# RoverWing-V4b.net
KiCad netlist of a schematic drawn in EAGLE
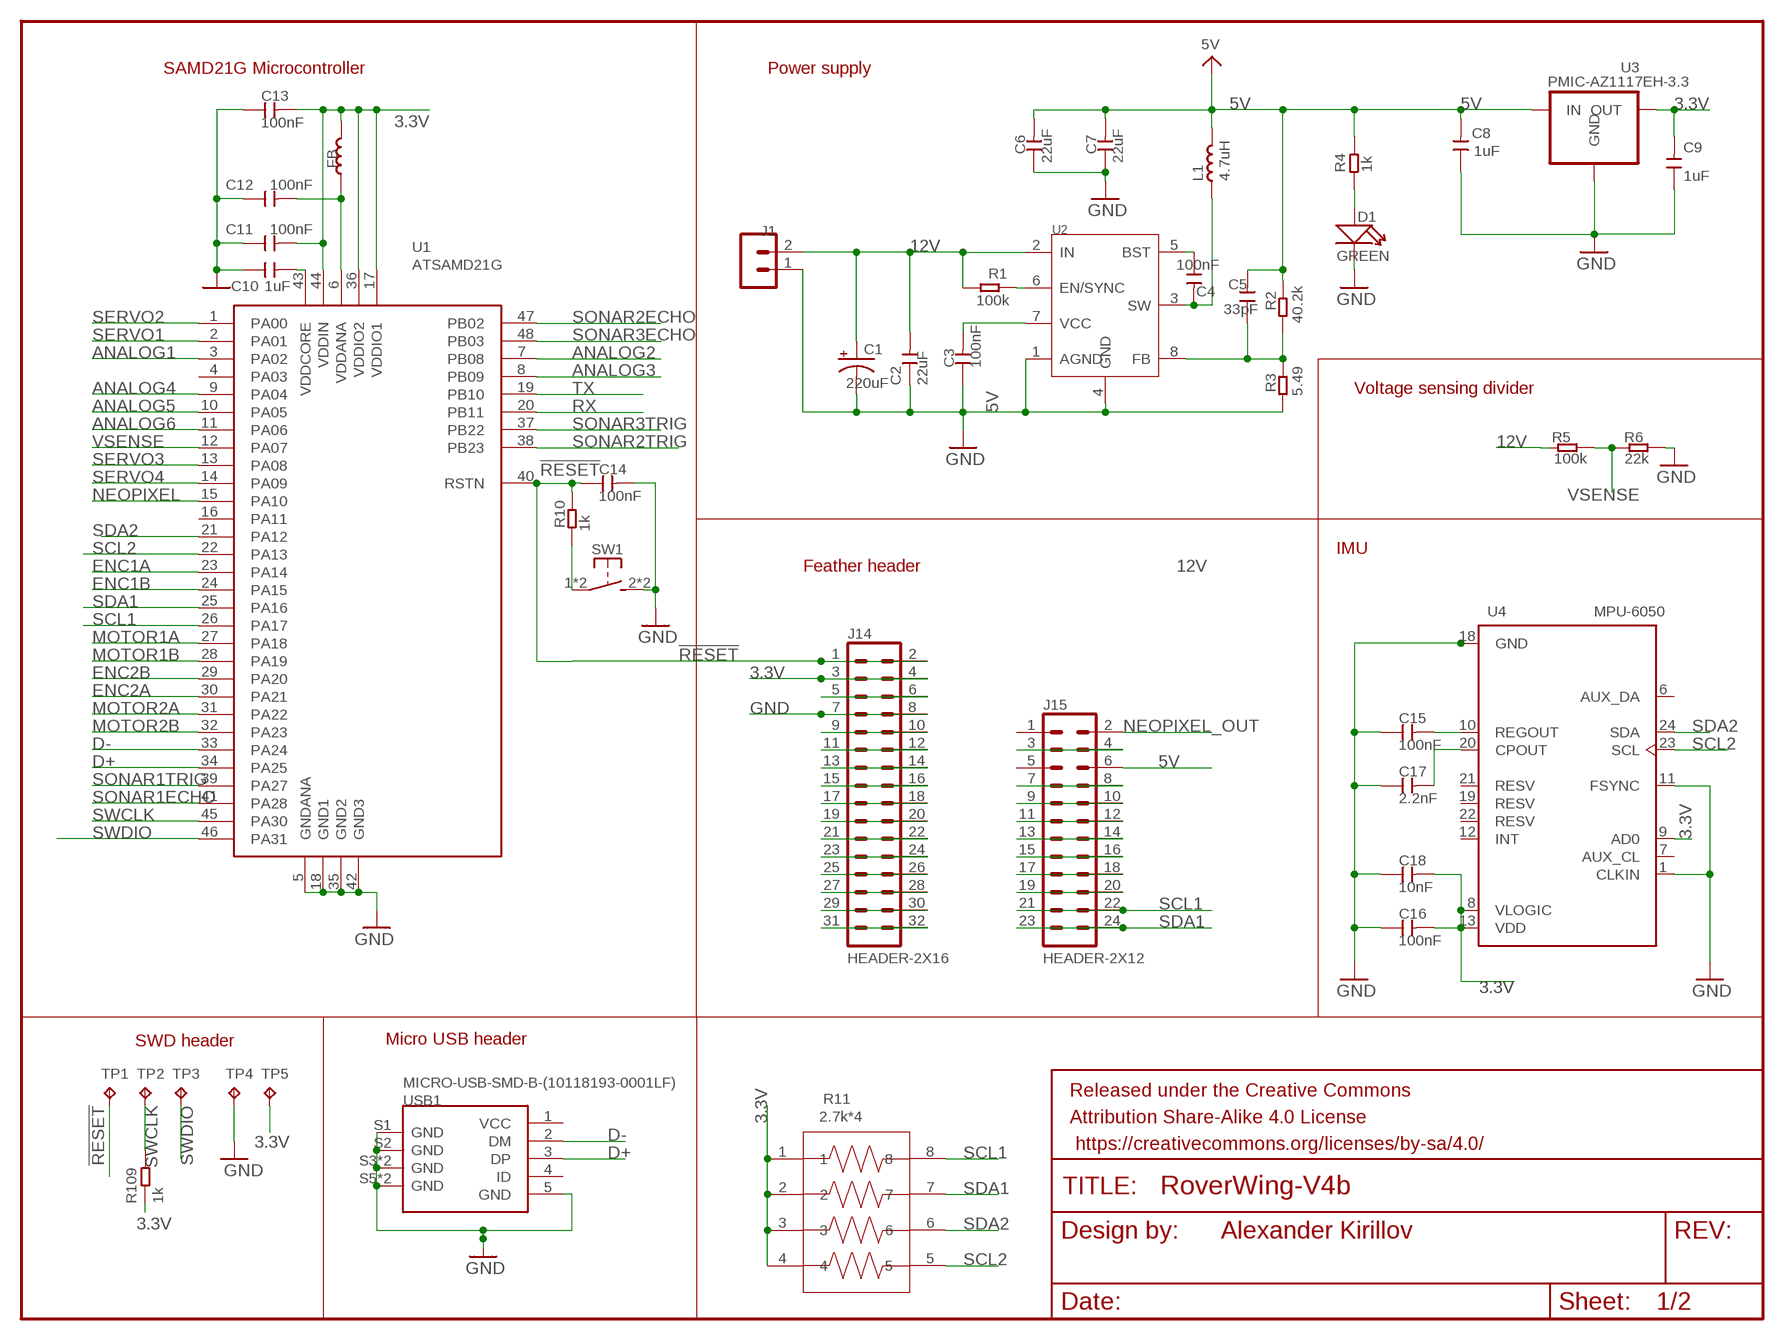
[diagram p0: schematic, sheet 1]
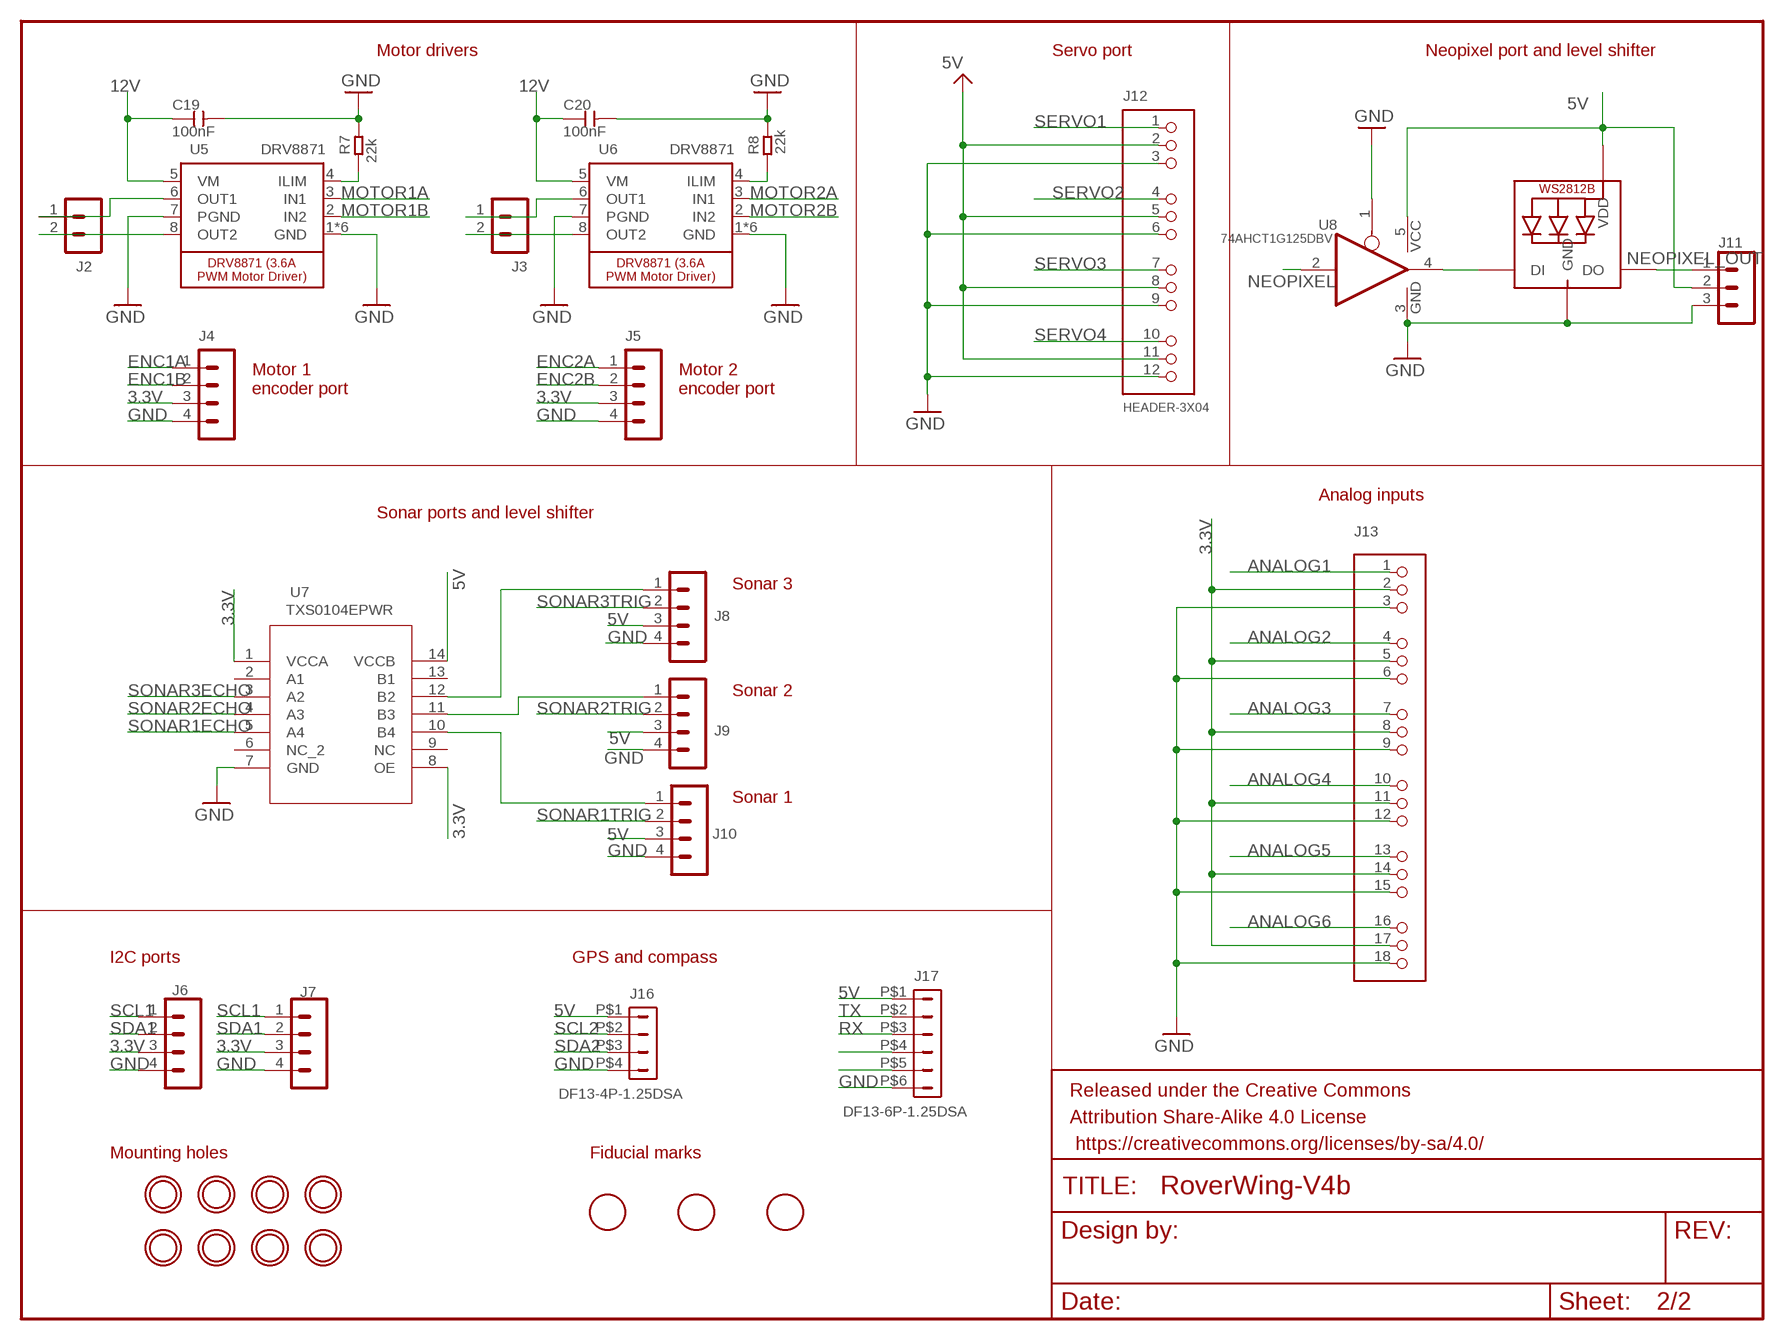
[diagram p1: schematic, sheet 2]

(export (version "E")
  (design (tool "Eeschema 10.0.6"))
  (components
    (comp (ref "C1")
      (value "220uF")
      (footprint "eagle-import:CAP-8X10.5")
      (libsource (lib "eagle-import") (part "CAP-POL-SMD-8X10.5"))
    )
    (comp (ref "C2")
      (value "22uF")
      (footprint "eagle-import:0805")
      (libsource (lib "eagle-import") (part "CAP-CERAMIC-SMD0805"))
    )
    (comp (ref "C3")
      (value "100nF")
      (footprint "eagle-import:0805")
      (libsource (lib "eagle-import") (part "CAP-CERAMIC-SMD0805"))
    )
    (comp (ref "C4")
      (value "100nF")
      (footprint "eagle-import:0805")
      (libsource (lib "eagle-import") (part "CAP-CERAMIC-SMD0805"))
    )
    (comp (ref "C5")
      (value "33pF")
      (footprint "eagle-import:0805")
      (libsource (lib "eagle-import") (part "CAP-CERAMIC-SMD0805"))
    )
    (comp (ref "C6")
      (value "22uF")
      (footprint "eagle-import:0805")
      (libsource (lib "eagle-import") (part "CAP-CERAMIC-SMD0805"))
    )
    (comp (ref "C7")
      (value "22uF")
      (footprint "eagle-import:0805")
      (libsource (lib "eagle-import") (part "CAP-CERAMIC-SMD0805"))
    )
    (comp (ref "C8")
      (value "1uF")
      (footprint "eagle-import:0805")
      (libsource (lib "eagle-import") (part "CAP-CERAMIC-SMD0805"))
    )
    (comp (ref "C9")
      (value "1uF")
      (footprint "eagle-import:0805")
      (libsource (lib "eagle-import") (part "CAP-CERAMIC-SMD0805"))
    )
    (comp (ref "C10")
      (value "1uF")
      (footprint "eagle-import:0805")
      (libsource (lib "eagle-import") (part "CAP-CERAMIC-SMD0805"))
    )
    (comp (ref "C11")
      (value "100nF")
      (footprint "eagle-import:0805")
      (libsource (lib "eagle-import") (part "CAP-CERAMIC-SMD0805"))
    )
    (comp (ref "C12")
      (value "100nF")
      (footprint "eagle-import:0805")
      (libsource (lib "eagle-import") (part "CAP-CERAMIC-SMD0805"))
    )
    (comp (ref "C13")
      (value "100nF")
      (footprint "eagle-import:0805")
      (libsource (lib "eagle-import") (part "CAP-CERAMIC-SMD0805"))
    )
    (comp (ref "C14")
      (value "100nF")
      (footprint "eagle-import:0805")
      (libsource (lib "eagle-import") (part "CAP-CERAMIC-SMD0805"))
    )
    (comp (ref "C15")
      (value "100nF")
      (footprint "eagle-import:0805")
      (libsource (lib "eagle-import") (part "CAP-CERAMIC-SMD0805"))
    )
    (comp (ref "C16")
      (value "100nF")
      (footprint "eagle-import:0805")
      (libsource (lib "eagle-import") (part "CAP-CERAMIC-SMD0805"))
    )
    (comp (ref "C17")
      (value "2.2nF")
      (footprint "eagle-import:0805")
      (libsource (lib "eagle-import") (part "CAP-CERAMIC-SMD0805"))
    )
    (comp (ref "C18")
      (value "10nF")
      (footprint "eagle-import:0805")
      (libsource (lib "eagle-import") (part "CAP-CERAMIC-SMD0805"))
    )
    (comp (ref "D1")
      (value "GREEN")
      (footprint "eagle-import:LED-0805")
      (libsource (lib "eagle-import") (part "SMD-LED-0805"))
    )
    (comp (ref "FB")
      (value "330R-1500MA")
      (footprint "eagle-import:0805")
      (fields (field (name "PARTNO") "BLM21PG331SN1D"))
      (libsource (lib "eagle-import") (part "SMD-FERRITE-BEAD-330R-1500MA(0805)"))
    )
    (comp (ref "FRAME2")
      (value "FRAME-LETTERNO_PACKAGE")
      (footprint "eagle-import:DUMMY")
      (libsource (lib "eagle-import") (part "FRAME-LETTERNO_PACKAGE"))
    )
    (comp (ref "J1")
      (value "HEADER-VH")
      (footprint "eagle-import:B2P-VH")
      (fields (field (name "PARTNO") "B2P-VH(LF)(SN)  "))
      (libsource (lib "eagle-import") (part "HEADER-VH"))
    )
    (comp (ref "J14")
      (value "HEADER-2X16")
      (footprint "eagle-import:2X16")
      (libsource (lib "eagle-import") (part "HEADER-2X16"))
    )
    (comp (ref "J15")
      (value "HEADER-2X12")
      (footprint "eagle-import:2X12")
      (libsource (lib "eagle-import") (part "HEADER-2X12"))
    )
    (comp (ref "L1")
      (value "4.7uH")
      (footprint "eagle-import:IND_TDK_7.1X6.5")
      (fields (field (name "MANUFACTURER") "TDK") (field (name "PARTNO") "SPM6530T-4R7M "))
      (libsource (lib "eagle-import") (part "IND-TDK-SPM6530T"))
    )
    (comp (ref "R1")
      (value "100k")
      (footprint "eagle-import:0805")
      (libsource (lib "eagle-import") (part "RES-SMD-0805"))
    )
    (comp (ref "R2")
      (value "40.2k")
      (footprint "eagle-import:0805")
      (libsource (lib "eagle-import") (part "RES-SMD-0805"))
    )
    (comp (ref "R3")
      (value "5.49")
      (footprint "eagle-import:0805")
      (libsource (lib "eagle-import") (part "RES-SMD-0805"))
    )
    (comp (ref "R4")
      (value "1k")
      (footprint "eagle-import:0805")
      (libsource (lib "eagle-import") (part "RES-SMD-0805"))
    )
    (comp (ref "R5")
      (value "100k")
      (footprint "eagle-import:0805")
      (libsource (lib "eagle-import") (part "RES-SMD-0805"))
    )
    (comp (ref "R6")
      (value "22k")
      (footprint "eagle-import:0805")
      (libsource (lib "eagle-import") (part "RES-SMD-0805"))
    )
    (comp (ref "R10")
      (value "1k")
      (footprint "eagle-import:0805")
      (libsource (lib "eagle-import") (part "RES-SMD-0805"))
    )
    (comp (ref "R11")
      (value "2.7k*4")
      (footprint "eagle-import:0603_4")
      (fields (field (name "PARTNO") "RTA03-4D272JTP "))
      (libsource (lib "eagle-import") (part "RES_ARRAY-2.7KX40603X4"))
    )
    (comp (ref "R109")
      (value "1k")
      (footprint "eagle-import:0805")
      (libsource (lib "eagle-import") (part "RES-SMD-0805"))
    )
    (comp (ref "SW1")
      (value "SW-TACTILE-4.5X4.5_SMD")
      (footprint "eagle-import:TL3305")
      (fields (field (name "MANUFACTURER") "BRIGHT") (field (name "PARTNO") "TSA453G38-250 "))
      (libsource (lib "eagle-import") (part "SW-TACTILE-4.5X4.5_SMD"))
    )
    (comp (ref "TP1")
      (value "TPTP15R")
      (footprint "eagle-import:TP15R")
      (libsource (lib "eagle-import") (part "TPTP15R"))
    )
    (comp (ref "TP2")
      (value "TPTP15R")
      (footprint "eagle-import:TP15R")
      (libsource (lib "eagle-import") (part "TPTP15R"))
    )
    (comp (ref "TP3")
      (value "TPTP15R")
      (footprint "eagle-import:TP15R")
      (libsource (lib "eagle-import") (part "TPTP15R"))
    )
    (comp (ref "TP4")
      (value "TPTP15R")
      (footprint "eagle-import:TP15R")
      (libsource (lib "eagle-import") (part "TPTP15R"))
    )
    (comp (ref "TP5")
      (value "TPTP15R")
      (footprint "eagle-import:TP15R")
      (libsource (lib "eagle-import") (part "TPTP15R"))
    )
    (comp (ref "U1")
      (value "ATSAMD21G")
      (footprint "eagle-import:TQFP-48-EDITED")
      (fields (field (name "MANUFACTURER") "Microchip Technology") (field (name "PARTNO") "ATSAMD21G18A-AU"))
      (libsource (lib "eagle-import") (part "ATSAMD21G"))
    )
    (comp (ref "U2")
      (value "PMIC-MP2225")
      (footprint "eagle-import:SOT-23-8")
      (fields (field (name "MANUFACTURER") "Monolithic Power Systems") (field (name "PARTNO") "MP2225GJ"))
      (libsource (lib "eagle-import") (part "PMIC-MP2225"))
    )
    (comp (ref "U3")
      (value "PMIC-AZ1117EH-3.3")
      (footprint "eagle-import:SOT223")
      (fields (field (name "PARTNO") "AZ1117EH-3.3TRG1"))
      (libsource (lib "eagle-import") (part "PMIC-AZ1117EH-3.3"))
    )
    (comp (ref "U4")
      (value "MPU-6050")
      (footprint "eagle-import:QFN50P400X400X95-24N")
      (fields (field (name "MANUFACTURER") "TDK InvenSense"))
      (libsource (lib "eagle-import") (part "MPU-6050"))
    )
    (comp (ref "USB1")
      (value "MICRO-USB-SMD-B-(10118193-0001LF)")
      (footprint "eagle-import:MICRO-USB5+6P-SMD-0.65-B")
      (fields (field (name "MANUFACTURER") "Amphenol ICC") (field (name "PARTNO") "10118193-0001LF"))
      (libsource (lib "eagle-import") (part "MICRO-USB-SMD-B-(10118193-0001LF)"))
    )
    (comp (ref "C19")
      (value "100nF")
      (footprint "eagle-import:0805")
      (libsource (lib "eagle-import") (part "CAP-CERAMIC-SMD0805"))
    )
    (comp (ref "C20")
      (value "100nF")
      (footprint "eagle-import:0805")
      (libsource (lib "eagle-import") (part "CAP-CERAMIC-SMD0805"))
    )
    (comp (ref "FRAME1")
      (value "FRAME-LETTERNO_PACKAGE")
      (footprint "eagle-import:DUMMY")
      (libsource (lib "eagle-import") (part "FRAME-LETTERNO_PACKAGE"))
    )
    (comp (ref "J2")
      (value "HEADER-VH")
      (footprint "eagle-import:B2P-VH")
      (fields (field (name "PARTNO") "B2P-VH(LF)(SN)  "))
      (libsource (lib "eagle-import") (part "HEADER-VH"))
    )
    (comp (ref "J3")
      (value "HEADER-VH")
      (footprint "eagle-import:B2P-VH")
      (fields (field (name "PARTNO") "B2P-VH(LF)(SN)  "))
      (libsource (lib "eagle-import") (part "HEADER-VH"))
    )
    (comp (ref "J4")
      (value "HEADER-PH-4P")
      (footprint "eagle-import:B4B-PH-K")
      (fields (field (name "PARTNO") "B4B-PH-K-S(LF)(SN)"))
      (libsource (lib "eagle-import") (part "HEADER-PH-4P"))
    )
    (comp (ref "J5")
      (value "HEADER-PH-4P")
      (footprint "eagle-import:B4B-PH-K")
      (fields (field (name "PARTNO") "B4B-PH-K-S(LF)(SN)"))
      (libsource (lib "eagle-import") (part "HEADER-PH-4P"))
    )
    (comp (ref "J6")
      (value "HEADER-PH-4P")
      (footprint "eagle-import:B4B-PH-K")
      (fields (field (name "PARTNO") "B4B-PH-K-S(LF)(SN)"))
      (libsource (lib "eagle-import") (part "HEADER-PH-4P"))
    )
    (comp (ref "J7")
      (value "HEADER-PH-4P")
      (footprint "eagle-import:B4B-PH-K")
      (fields (field (name "PARTNO") "B4B-PH-K-S(LF)(SN)"))
      (libsource (lib "eagle-import") (part "HEADER-PH-4P"))
    )
    (comp (ref "J8")
      (value "HEADER-PH-4P")
      (footprint "eagle-import:B4B-PH-K")
      (fields (field (name "PARTNO") "B4B-PH-K-S(LF)(SN)"))
      (libsource (lib "eagle-import") (part "HEADER-PH-4P"))
    )
    (comp (ref "J9")
      (value "HEADER-PH-4P")
      (footprint "eagle-import:B4B-PH-K")
      (fields (field (name "PARTNO") "B4B-PH-K-S(LF)(SN)"))
      (libsource (lib "eagle-import") (part "HEADER-PH-4P"))
    )
    (comp (ref "J10")
      (value "HEADER-PH-4P")
      (footprint "eagle-import:B4B-PH-K")
      (fields (field (name "PARTNO") "B4B-PH-K-S(LF)(SN)"))
      (libsource (lib "eagle-import") (part "HEADER-PH-4P"))
    )
    (comp (ref "J11")
      (value "HEADER-PH-3P")
      (footprint "eagle-import:B3B-PH-K")
      (fields (field (name "PARTNO") "B3B-PH-K-S(LF)(SN)"))
      (libsource (lib "eagle-import") (part "HEADER-PH-3P"))
    )
    (comp (ref "J12")
      (value "HEADER-3X04")
      (footprint "eagle-import:3X04")
      (libsource (lib "eagle-import") (part "HEADER-3X04"))
    )
    (comp (ref "J13")
      (value "HEADER-3X06\"")
      (footprint "eagle-import:3X06")
      (libsource (lib "eagle-import") (part "HEADER-3X06{dblquote}"))
    )
    (comp (ref "J16")
      (value "DF13-4P-1.25DSA")
      (footprint "eagle-import:DF13-4P-1.25DSA")
      (libsource (lib "eagle-import") (part "DF13-4P-1.25DSA"))
    )
    (comp (ref "J17")
      (value "DF13-6P-1.25DSA")
      (footprint "eagle-import:DF13-6P-1.25DSA")
      (libsource (lib "eagle-import") (part "DF13-6P-1.25DSA"))
    )
    (comp (ref "LED1")
      (value "WS2812B3535")
      (footprint "eagle-import:LED3535")
      (fields (field (name "MANUFACTURER") "Worldsemi") (field (name "PARTNO") "WS2812B-3535 "))
      (libsource (lib "eagle-import") (part "WS2812B3535"))
    )
    (comp (ref "R7")
      (value "22k")
      (footprint "eagle-import:0805")
      (libsource (lib "eagle-import") (part "RES-SMD-0805"))
    )
    (comp (ref "R8")
      (value "22k")
      (footprint "eagle-import:0805")
      (libsource (lib "eagle-import") (part "RES-SMD-0805"))
    )
    (comp (ref "U$3")
      (value "MOUNTINGHOLE3.0_NPH")
      (footprint "eagle-import:MOUNTINGHOLE_3.0_NPH")
      (libsource (lib "eagle-import") (part "MOUNTINGHOLE3.0_NPH"))
    )
    (comp (ref "U$4")
      (value "MOUNTINGHOLE3.0_NPH")
      (footprint "eagle-import:MOUNTINGHOLE_3.0_NPH")
      (libsource (lib "eagle-import") (part "MOUNTINGHOLE3.0_NPH"))
    )
    (comp (ref "U$11")
      (value "FIDUCIAL")
      (footprint "eagle-import:FIDUCIAL_1MM")
      (libsource (lib "eagle-import") (part "FIDUCIAL"))
    )
    (comp (ref "U$13")
      (value "FIDUCIAL")
      (footprint "eagle-import:FIDUCIAL_1MM")
      (libsource (lib "eagle-import") (part "FIDUCIAL"))
    )
    (comp (ref "U$14")
      (value "MOUNTINGHOLE3.0_NPH")
      (footprint "eagle-import:MOUNTINGHOLE_3.0_NPH")
      (libsource (lib "eagle-import") (part "MOUNTINGHOLE3.0_NPH"))
    )
    (comp (ref "U$15")
      (value "MOUNTINGHOLE3.0_NPH")
      (footprint "eagle-import:MOUNTINGHOLE_3.0_NPH")
      (libsource (lib "eagle-import") (part "MOUNTINGHOLE3.0_NPH"))
    )
    (comp (ref "U$17")
      (value "FIDUCIAL")
      (footprint "eagle-import:FIDUCIAL_1MM")
      (libsource (lib "eagle-import") (part "FIDUCIAL"))
    )
    (comp (ref "U$24")
      (value "MOUNTINGHOLE3.0_NPH")
      (footprint "eagle-import:MOUNTINGHOLE_3.0_NPH")
      (libsource (lib "eagle-import") (part "MOUNTINGHOLE3.0_NPH"))
    )
    (comp (ref "U$25")
      (value "MOUNTINGHOLE3.0_NPH")
      (footprint "eagle-import:MOUNTINGHOLE_3.0_NPH")
      (libsource (lib "eagle-import") (part "MOUNTINGHOLE3.0_NPH"))
    )
    (comp (ref "U$26")
      (value "MOUNTINGHOLE3.0_NPH")
      (footprint "eagle-import:MOUNTINGHOLE_3.0_NPH")
      (libsource (lib "eagle-import") (part "MOUNTINGHOLE3.0_NPH"))
    )
    (comp (ref "U$27")
      (value "MOUNTINGHOLE3.0_NPH")
      (footprint "eagle-import:MOUNTINGHOLE_3.0_NPH")
      (libsource (lib "eagle-import") (part "MOUNTINGHOLE3.0_NPH"))
    )
    (comp (ref "U5")
      (value "DRV8871")
      (footprint "eagle-import:HSOP8")
      (fields (field (name "MANUFACTURER") "TEXAS INSTRUMENTS") (field (name "PARTNO") "DRV8871DDAR"))
      (libsource (lib "eagle-import") (part "DRV8871"))
    )
    (comp (ref "U6")
      (value "DRV8871")
      (footprint "eagle-import:HSOP8")
      (fields (field (name "MANUFACTURER") "TEXAS INSTRUMENTS") (field (name "PARTNO") "DRV8871DDAR"))
      (libsource (lib "eagle-import") (part "DRV8871"))
    )
    (comp (ref "U7")
      (value "TXS0104EPWR")
      (footprint "eagle-import:PW14")
      (fields (field (name "MANUFACTURER") "Texas Instruments"))
      (libsource (lib "eagle-import") (part "TXS0104EPWR"))
    )
    (comp (ref "U8")
      (value "74AHCT1G125DBV")
      (footprint "eagle-import:SOT23-5")
      (fields (field (name "PARTNO") "SN74AHCT1G125DBVR"))
      (libsource (lib "eagle-import") (part "741G125DBVAHCT"))
    )
  )
  (nets
    (net (code "1") (name "3.3V") (class "Default")
      (node (ref "C11") (pin "2") (pinfunction "2_2") (pintype "passive"))
      (node (ref "C13") (pin "2") (pinfunction "2_2") (pintype "passive"))
      (node (ref "C16") (pin "2") (pinfunction "2_2") (pintype "passive"))
      (node (ref "C18") (pin "2") (pinfunction "2_2") (pintype "passive"))
      (node (ref "C9") (pin "2") (pinfunction "2_2") (pintype "passive"))
      (node (ref "FB") (pin "2") (pinfunction "2_2") (pintype "passive"))
      (node (ref "J13") (pin "11") (pinfunction "11_11") (pintype "passive"))
      (node (ref "J13") (pin "14") (pinfunction "14_14") (pintype "passive"))
      (node (ref "J13") (pin "17") (pinfunction "17_17") (pintype "passive"))
      (node (ref "J13") (pin "2") (pinfunction "2_2") (pintype "passive"))
      (node (ref "J13") (pin "5") (pinfunction "5_5") (pintype "passive"))
      (node (ref "J13") (pin "8") (pinfunction "8_8") (pintype "passive"))
      (node (ref "J14") (pin "3") (pinfunction "3_3") (pintype "passive"))
      (node (ref "J14") (pin "4") (pinfunction "4_4") (pintype "passive"))
      (node (ref "J4") (pin "3") (pinfunction "3_3") (pintype "passive"))
      (node (ref "J5") (pin "3") (pinfunction "3_3") (pintype "passive"))
      (node (ref "J6") (pin "3") (pinfunction "3_3") (pintype "passive"))
      (node (ref "J7") (pin "3") (pinfunction "3_3") (pintype "passive"))
      (node (ref "R109") (pin "1") (pinfunction "1_1") (pintype "passive"))
      (node (ref "R11") (pin "1") (pinfunction "1_1") (pintype "passive"))
      (node (ref "R11") (pin "2") (pinfunction "2_2") (pintype "passive"))
      (node (ref "R11") (pin "3") (pinfunction "3_3") (pintype "passive"))
      (node (ref "R11") (pin "4") (pinfunction "4_4") (pintype "passive"))
      (node (ref "TP5") (pin "TP") (pinfunction "TP_TP") (pintype "input"))
      (node (ref "U1") (pin "17") (pinfunction "VDDIO1_17") (pintype "power_in"))
      (node (ref "U1") (pin "36") (pinfunction "VDDIO2_36") (pintype "power_in"))
      (node (ref "U1") (pin "44") (pinfunction "VDDIN_44") (pintype "power_in"))
      (node (ref "U3") (pin "2") (pinfunction "OUT_2") (pintype "output"))
      (node (ref "U3") (pin "4") (pinfunction "OUT_4") (pintype "output"))
      (node (ref "U4") (pin "13") (pinfunction "VDD_13") (pintype "power_in"))
      (node (ref "U4") (pin "8") (pinfunction "VLOGIC_8") (pintype "power_in"))
      (node (ref "U4") (pin "9") (pinfunction "AD0_9") (pintype "input"))
      (node (ref "U7") (pin "1") (pinfunction "VCCA_1") (pintype "power_in"))
      (node (ref "U7") (pin "8") (pinfunction "OE_8") (pintype "output"))
    )
    (net (code "2") (name "5V") (class "Default")
      (node (ref "C5") (pin "2") (pinfunction "2_2") (pintype "passive"))
      (node (ref "C6") (pin "2") (pinfunction "2_2") (pintype "passive"))
      (node (ref "C7") (pin "2") (pinfunction "2_2") (pintype "passive"))
      (node (ref "C8") (pin "2") (pinfunction "2_2") (pintype "passive"))
      (node (ref "J10") (pin "3") (pinfunction "3_3") (pintype "passive"))
      (node (ref "J11") (pin "2") (pinfunction "2_2") (pintype "passive"))
      (node (ref "J12") (pin "11") (pinfunction "11_11") (pintype "passive"))
      (node (ref "J12") (pin "2") (pinfunction "2_2") (pintype "passive"))
      (node (ref "J12") (pin "5") (pinfunction "5_5") (pintype "passive"))
      (node (ref "J12") (pin "8") (pinfunction "8_8") (pintype "passive"))
      (node (ref "J15") (pin "6") (pinfunction "6_6") (pintype "passive"))
      (node (ref "J16") (pin "P$1") (pinfunction "1_P$1") (pintype "passive"))
      (node (ref "J17") (pin "P$1") (pinfunction "1_P$1") (pintype "passive"))
      (node (ref "J8") (pin "3") (pinfunction "3_3") (pintype "passive"))
      (node (ref "J9") (pin "3") (pinfunction "3_3") (pintype "passive"))
      (node (ref "L1") (pin "2") (pinfunction "2_2") (pintype "passive"))
      (node (ref "LED1") (pin "2") (pinfunction "VDD_2") (pintype "power_in"))
      (node (ref "R2") (pin "1") (pinfunction "1_1") (pintype "passive"))
      (node (ref "R4") (pin "2") (pinfunction "2_2") (pintype "passive"))
      (node (ref "U3") (pin "3") (pinfunction "IN_3") (pintype "input"))
      (node (ref "U7") (pin "14") (pinfunction "VCCB_14") (pintype "power_in"))
      (node (ref "U8") (pin "5") (pinfunction "VCC_5") (pintype "power_in"))
    )
    (net (code "3") (name "12V") (class "Default")
      (node (ref "C1") (pin "+") (pinfunction "+_+") (pintype "passive"))
      (node (ref "C19") (pin "1") (pinfunction "1_1") (pintype "passive"))
      (node (ref "C2") (pin "2") (pinfunction "2_2") (pintype "passive"))
      (node (ref "C20") (pin "1") (pinfunction "1_1") (pintype "passive"))
      (node (ref "J1") (pin "2") (pinfunction "2_2") (pintype "passive"))
      (node (ref "R1") (pin "2") (pinfunction "2_2") (pintype "passive"))
      (node (ref "R5") (pin "2") (pinfunction "2_2") (pintype "passive"))
      (node (ref "U2") (pin "2") (pinfunction "IN_2") (pintype "bidirectional"))
      (node (ref "U5") (pin "5") (pinfunction "VM_5") (pintype "power_in"))
      (node (ref "U6") (pin "5") (pinfunction "VM_5") (pintype "power_in"))
    )
    (net (code "4") (name "ANALOG1") (class "Default")
      (node (ref "J13") (pin "1") (pinfunction "1_1") (pintype "passive"))
      (node (ref "U1") (pin "3") (pinfunction "PA02_3") (pintype "bidirectional"))
    )
    (net (code "5") (name "ANALOG2") (class "Default")
      (node (ref "J13") (pin "4") (pinfunction "4_4") (pintype "passive"))
      (node (ref "U1") (pin "7") (pinfunction "PB08_7") (pintype "bidirectional"))
    )
    (net (code "6") (name "ANALOG3") (class "Default")
      (node (ref "J13") (pin "7") (pinfunction "7_7") (pintype "passive"))
      (node (ref "U1") (pin "8") (pinfunction "PB09_8") (pintype "bidirectional"))
    )
    (net (code "7") (name "ANALOG4") (class "Default")
      (node (ref "J13") (pin "10") (pinfunction "10_10") (pintype "passive"))
      (node (ref "U1") (pin "9") (pinfunction "PA04_9") (pintype "bidirectional"))
    )
    (net (code "8") (name "ANALOG5") (class "Default")
      (node (ref "J13") (pin "13") (pinfunction "13_13") (pintype "passive"))
      (node (ref "U1") (pin "10") (pinfunction "PA05_10") (pintype "bidirectional"))
    )
    (net (code "9") (name "ANALOG6") (class "Default")
      (node (ref "J13") (pin "16") (pinfunction "16_16") (pintype "passive"))
      (node (ref "U1") (pin "11") (pinfunction "PA06_11") (pintype "bidirectional"))
    )
    (net (code "10") (name "D+") (class "Default")
      (node (ref "U1") (pin "34") (pinfunction "PA25_34") (pintype "bidirectional"))
      (node (ref "USB1") (pin "3") (pinfunction "DP_3") (pintype "bidirectional"))
    )
    (net (code "11") (name "D-") (class "Default")
      (node (ref "U1") (pin "33") (pinfunction "PA24_33") (pintype "bidirectional"))
      (node (ref "USB1") (pin "2") (pinfunction "DM_2") (pintype "bidirectional"))
    )
    (net (code "12") (name "ENC1A") (class "Default")
      (node (ref "J4") (pin "1") (pinfunction "1_1") (pintype "passive"))
      (node (ref "U1") (pin "23") (pinfunction "PA14_23") (pintype "bidirectional"))
    )
    (net (code "13") (name "ENC1B") (class "Default")
      (node (ref "J4") (pin "2") (pinfunction "2_2") (pintype "passive"))
      (node (ref "U1") (pin "24") (pinfunction "PA15_24") (pintype "bidirectional"))
    )
    (net (code "14") (name "ENC2A") (class "Default")
      (node (ref "J5") (pin "1") (pinfunction "1_1") (pintype "passive"))
      (node (ref "U1") (pin "30") (pinfunction "PA21_30") (pintype "bidirectional"))
    )
    (net (code "15") (name "ENC2B") (class "Default")
      (node (ref "J5") (pin "2") (pinfunction "2_2") (pintype "passive"))
      (node (ref "U1") (pin "29") (pinfunction "PA20_29") (pintype "bidirectional"))
    )
    (net (code "16") (name "GND") (class "Default")
      (node (ref "C1") (pin "-") (pinfunction "-_-") (pintype "passive"))
      (node (ref "C10") (pin "1") (pinfunction "1_1") (pintype "passive"))
      (node (ref "C11") (pin "1") (pinfunction "1_1") (pintype "passive"))
      (node (ref "C12") (pin "1") (pinfunction "1_1") (pintype "passive"))
      (node (ref "C13") (pin "1") (pinfunction "1_1") (pintype "passive"))
      (node (ref "C14") (pin "2") (pinfunction "2_2") (pintype "passive"))
      (node (ref "C15") (pin "1") (pinfunction "1_1") (pintype "passive"))
      (node (ref "C16") (pin "1") (pinfunction "1_1") (pintype "passive"))
      (node (ref "C17") (pin "1") (pinfunction "1_1") (pintype "passive"))
      (node (ref "C18") (pin "1") (pinfunction "1_1") (pintype "passive"))
      (node (ref "C19") (pin "2") (pinfunction "2_2") (pintype "passive"))
      (node (ref "C2") (pin "1") (pinfunction "1_1") (pintype "passive"))
      (node (ref "C20") (pin "2") (pinfunction "2_2") (pintype "passive"))
      (node (ref "C3") (pin "1") (pinfunction "1_1") (pintype "passive"))
      (node (ref "C6") (pin "1") (pinfunction "1_1") (pintype "passive"))
      (node (ref "C7") (pin "1") (pinfunction "1_1") (pintype "passive"))
      (node (ref "C8") (pin "1") (pinfunction "1_1") (pintype "passive"))
      (node (ref "C9") (pin "1") (pinfunction "1_1") (pintype "passive"))
      (node (ref "D1") (pin "-") (pinfunction "-_-") (pintype "passive"))
      (node (ref "J1") (pin "1") (pinfunction "1_1") (pintype "passive"))
      (node (ref "J10") (pin "4") (pinfunction "4_4") (pintype "passive"))
      (node (ref "J11") (pin "3") (pinfunction "3_3") (pintype "passive"))
      (node (ref "J12") (pin "12") (pinfunction "12_12") (pintype "passive"))
      (node (ref "J12") (pin "3") (pinfunction "3_3") (pintype "passive"))
      (node (ref "J12") (pin "6") (pinfunction "6_6") (pintype "passive"))
      (node (ref "J12") (pin "9") (pinfunction "9_9") (pintype "passive"))
      (node (ref "J13") (pin "12") (pinfunction "12_12") (pintype "passive"))
      (node (ref "J13") (pin "15") (pinfunction "15_15") (pintype "passive"))
      (node (ref "J13") (pin "18") (pinfunction "18_18") (pintype "passive"))
      (node (ref "J13") (pin "3") (pinfunction "3_3") (pintype "passive"))
      (node (ref "J13") (pin "6") (pinfunction "6_6") (pintype "passive"))
      (node (ref "J13") (pin "9") (pinfunction "9_9") (pintype "passive"))
      (node (ref "J14") (pin "7") (pinfunction "7_7") (pintype "passive"))
      (node (ref "J14") (pin "8") (pinfunction "8_8") (pintype "passive"))
      (node (ref "J16") (pin "P$4") (pinfunction "4_P$4") (pintype "passive"))
      (node (ref "J17") (pin "P$6") (pinfunction "6_P$6") (pintype "passive"))
      (node (ref "J4") (pin "4") (pinfunction "4_4") (pintype "passive"))
      (node (ref "J5") (pin "4") (pinfunction "4_4") (pintype "passive"))
      (node (ref "J6") (pin "4") (pinfunction "4_4") (pintype "passive"))
      (node (ref "J7") (pin "4") (pinfunction "4_4") (pintype "passive"))
      (node (ref "J8") (pin "4") (pinfunction "4_4") (pintype "passive"))
      (node (ref "J9") (pin "4") (pinfunction "4_4") (pintype "passive"))
      (node (ref "LED1") (pin "4") (pinfunction "GND_4") (pintype "power_in"))
      (node (ref "R3") (pin "2") (pinfunction "2_2") (pintype "passive"))
      (node (ref "R6") (pin "2") (pinfunction "2_2") (pintype "passive"))
      (node (ref "R7") (pin "2") (pinfunction "2_2") (pintype "passive"))
      (node (ref "R8") (pin "2") (pinfunction "2_2") (pintype "passive"))
      (node (ref "SW1") (pin "2") (pinfunction "S1_2") (pintype "passive"))
      (node (ref "SW1") (pin "3") (pinfunction "S1_3") (pintype "passive"))
      (node (ref "TP4") (pin "TP") (pinfunction "TP_TP") (pintype "input"))
      (node (ref "U1") (pin "18") (pinfunction "GND1_18") (pintype "power_in"))
      (node (ref "U1") (pin "35") (pinfunction "GND2_35") (pintype "power_in"))
      (node (ref "U1") (pin "42") (pinfunction "GND3_42") (pintype "power_in"))
      (node (ref "U1") (pin "5") (pinfunction "GNDANA_5") (pintype "power_in"))
      (node (ref "U2") (pin "1") (pinfunction "AGND_1") (pintype "bidirectional"))
      (node (ref "U2") (pin "4") (pinfunction "GND_4") (pintype "bidirectional"))
      (node (ref "U3") (pin "1") (pinfunction "GND_1") (pintype "power_in"))
      (node (ref "U4") (pin "1") (pinfunction "CLKIN_1") (pintype "input"))
      (node (ref "U4") (pin "11") (pinfunction "FSYNC_11") (pintype "input"))
      (node (ref "U4") (pin "18") (pinfunction "GND_18") (pintype "power_in"))
      (node (ref "U5") (pin "1") (pinfunction "GND_1") (pintype "power_in"))
      (node (ref "U5") (pin "7") (pinfunction "PGND_7") (pintype "power_in"))
      (node (ref "U5") (pin "GND") (pinfunction "GND_GND") (pintype "power_in"))
      (node (ref "U5") (pin "P$1") (pinfunction "GND_P$1") (pintype "power_in"))
      (node (ref "U5") (pin "P$2") (pinfunction "GND_P$2") (pintype "power_in"))
      (node (ref "U5") (pin "P$3") (pinfunction "GND_P$3") (pintype "power_in"))
      (node (ref "U5") (pin "P$4") (pinfunction "GND_P$4") (pintype "power_in"))
      (node (ref "U6") (pin "1") (pinfunction "GND_1") (pintype "power_in"))
      (node (ref "U6") (pin "7") (pinfunction "PGND_7") (pintype "power_in"))
      (node (ref "U6") (pin "GND") (pinfunction "GND_GND") (pintype "power_in"))
      (node (ref "U6") (pin "P$1") (pinfunction "GND_P$1") (pintype "power_in"))
      (node (ref "U6") (pin "P$2") (pinfunction "GND_P$2") (pintype "power_in"))
      (node (ref "U6") (pin "P$3") (pinfunction "GND_P$3") (pintype "power_in"))
      (node (ref "U6") (pin "P$4") (pinfunction "GND_P$4") (pintype "power_in"))
      (node (ref "U7") (pin "7") (pinfunction "GND_7") (pintype "power_in"))
      (node (ref "U8") (pin "1") (pinfunction "OE_1") (pintype "input"))
      (node (ref "U8") (pin "3") (pinfunction "GND_3") (pintype "power_in"))
      (node (ref "USB1") (pin "5") (pinfunction "GND_5") (pintype "bidirectional"))
      (node (ref "USB1") (pin "S1") (pinfunction "GND_S1") (pintype "bidirectional"))
      (node (ref "USB1") (pin "S2") (pinfunction "GND_S2") (pintype "bidirectional"))
      (node (ref "USB1") (pin "S3") (pinfunction "GND_S3") (pintype "bidirectional"))
      (node (ref "USB1") (pin "S4") (pinfunction "GND_S4") (pintype "bidirectional"))
      (node (ref "USB1") (pin "S5") (pinfunction "GND_S5") (pintype "bidirectional"))
      (node (ref "USB1") (pin "S6") (pinfunction "GND_S6") (pintype "bidirectional"))
    )
    (net (code "17") (name "MOTOR1A") (class "Default")
      (node (ref "U1") (pin "27") (pinfunction "PA18_27") (pintype "bidirectional"))
      (node (ref "U5") (pin "3") (pinfunction "IN1_3") (pintype "input"))
    )
    (net (code "18") (name "MOTOR1B") (class "Default")
      (node (ref "U1") (pin "28") (pinfunction "PA19_28") (pintype "bidirectional"))
      (node (ref "U5") (pin "2") (pinfunction "IN2_2") (pintype "input"))
    )
    (net (code "19") (name "MOTOR2A") (class "Default")
      (node (ref "U1") (pin "31") (pinfunction "PA22_31") (pintype "bidirectional"))
      (node (ref "U6") (pin "3") (pinfunction "IN1_3") (pintype "input"))
    )
    (net (code "20") (name "MOTOR2B") (class "Default")
      (node (ref "U1") (pin "32") (pinfunction "PA23_32") (pintype "bidirectional"))
      (node (ref "U6") (pin "2") (pinfunction "IN2_2") (pintype "input"))
    )
    (net (code "21") (name "NEOPIXEL") (class "Default")
      (node (ref "U1") (pin "15") (pinfunction "PA10_15") (pintype "bidirectional"))
      (node (ref "U8") (pin "2") (pinfunction "I_2") (pintype "input"))
    )
    (net (code "22") (name "NEOPIXEL_OUT") (class "Default")
      (node (ref "J11") (pin "1") (pinfunction "1_1") (pintype "passive"))
      (node (ref "J15") (pin "2") (pinfunction "2_2") (pintype "passive"))
      (node (ref "LED1") (pin "3") (pinfunction "DO_3") (pintype "output"))
    )
    (net (code "23") (name "Net-(D1-Pad+)") (class "Default")
      (node (ref "D1") (pin "+") (pinfunction "+_+") (pintype "passive"))
      (node (ref "R4") (pin "1") (pinfunction "1_1") (pintype "passive"))
    )
    (net (code "24") (name "Net-(J14-Pad5)") (class "Default")
      (node (ref "J14") (pin "5") (pinfunction "5_5") (pintype "passive"))
      (node (ref "J14") (pin "6") (pinfunction "6_6") (pintype "passive"))
    )
    (net (code "25") (name "Net-(J14-Pad10)") (class "Default")
      (node (ref "J14") (pin "10") (pinfunction "10_10") (pintype "passive"))
      (node (ref "J14") (pin "9") (pinfunction "9_9") (pintype "passive"))
    )
    (net (code "26") (name "Net-(J14-Pad11)") (class "Default")
      (node (ref "J14") (pin "11") (pinfunction "11_11") (pintype "passive"))
      (node (ref "J14") (pin "12") (pinfunction "12_12") (pintype "passive"))
    )
    (net (code "27") (name "Net-(J14-Pad13)") (class "Default")
      (node (ref "J14") (pin "13") (pinfunction "13_13") (pintype "passive"))
      (node (ref "J14") (pin "14") (pinfunction "14_14") (pintype "passive"))
    )
    (net (code "28") (name "Net-(J14-Pad15)") (class "Default")
      (node (ref "J14") (pin "15") (pinfunction "15_15") (pintype "passive"))
      (node (ref "J14") (pin "16") (pinfunction "16_16") (pintype "passive"))
    )
    (net (code "29") (name "Net-(J14-Pad17)") (class "Default")
      (node (ref "J14") (pin "17") (pinfunction "17_17") (pintype "passive"))
      (node (ref "J14") (pin "18") (pinfunction "18_18") (pintype "passive"))
    )
    (net (code "30") (name "Net-(J14-Pad19)") (class "Default")
      (node (ref "J14") (pin "19") (pinfunction "19_19") (pintype "passive"))
      (node (ref "J14") (pin "20") (pinfunction "20_20") (pintype "passive"))
    )
    (net (code "31") (name "Net-(J14-Pad21)") (class "Default")
      (node (ref "J14") (pin "21") (pinfunction "21_21") (pintype "passive"))
      (node (ref "J14") (pin "22") (pinfunction "22_22") (pintype "passive"))
    )
    (net (code "32") (name "Net-(J14-Pad23)") (class "Default")
      (node (ref "J14") (pin "23") (pinfunction "23_23") (pintype "passive"))
      (node (ref "J14") (pin "24") (pinfunction "24_24") (pintype "passive"))
    )
    (net (code "33") (name "Net-(J14-Pad25)") (class "Default")
      (node (ref "J14") (pin "25") (pinfunction "25_25") (pintype "passive"))
      (node (ref "J14") (pin "26") (pinfunction "26_26") (pintype "passive"))
    )
    (net (code "34") (name "Net-(J14-Pad27)") (class "Default")
      (node (ref "J14") (pin "27") (pinfunction "27_27") (pintype "passive"))
      (node (ref "J14") (pin "28") (pinfunction "28_28") (pintype "passive"))
    )
    (net (code "35") (name "Net-(J14-Pad29)") (class "Default")
      (node (ref "J14") (pin "29") (pinfunction "29_29") (pintype "passive"))
      (node (ref "J14") (pin "30") (pinfunction "30_30") (pintype "passive"))
    )
    (net (code "36") (name "Net-(J14-Pad31)") (class "Default")
      (node (ref "J14") (pin "31") (pinfunction "31_31") (pintype "passive"))
      (node (ref "J14") (pin "32") (pinfunction "32_32") (pintype "passive"))
    )
    (net (code "37") (name "Net-(J15-Pad3)") (class "Default")
      (node (ref "J15") (pin "3") (pinfunction "3_3") (pintype "passive"))
      (node (ref "J15") (pin "4") (pinfunction "4_4") (pintype "passive"))
    )
    (net (code "38") (name "Net-(J15-Pad7)") (class "Default")
      (node (ref "J15") (pin "7") (pinfunction "7_7") (pintype "passive"))
      (node (ref "J15") (pin "8") (pinfunction "8_8") (pintype "passive"))
    )
    (net (code "39") (name "Net-(J15-Pad10)") (class "Default")
      (node (ref "J15") (pin "10") (pinfunction "10_10") (pintype "passive"))
      (node (ref "J15") (pin "9") (pinfunction "9_9") (pintype "passive"))
    )
    (net (code "40") (name "Net-(J15-Pad11)") (class "Default")
      (node (ref "J15") (pin "11") (pinfunction "11_11") (pintype "passive"))
      (node (ref "J15") (pin "12") (pinfunction "12_12") (pintype "passive"))
    )
    (net (code "41") (name "Net-(J15-Pad13)") (class "Default")
      (node (ref "J15") (pin "13") (pinfunction "13_13") (pintype "passive"))
      (node (ref "J15") (pin "14") (pinfunction "14_14") (pintype "passive"))
    )
    (net (code "42") (name "Net-(J15-Pad15)") (class "Default")
      (node (ref "J15") (pin "15") (pinfunction "15_15") (pintype "passive"))
      (node (ref "J15") (pin "16") (pinfunction "16_16") (pintype "passive"))
    )
    (net (code "43") (name "Net-(J15-Pad17)") (class "Default")
      (node (ref "J15") (pin "17") (pinfunction "17_17") (pintype "passive"))
      (node (ref "J15") (pin "18") (pinfunction "18_18") (pintype "passive"))
    )
    (net (code "44") (name "Net-(J15-Pad19)") (class "Default")
      (node (ref "J15") (pin "19") (pinfunction "19_19") (pintype "passive"))
      (node (ref "J15") (pin "20") (pinfunction "20_20") (pintype "passive"))
    )
    (net (code "45") (name "Net-(LED1-DI)") (class "Default")
      (node (ref "LED1") (pin "1") (pinfunction "DI_1") (pintype "input"))
      (node (ref "U8") (pin "4") (pinfunction "O_4") (pintype "tri_state"))
    )
    (net (code "46") (name "Net-(R10-Pad1)") (class "Default")
      (node (ref "R10") (pin "1") (pinfunction "1_1") (pintype "passive"))
      (node (ref "SW1") (pin "1") (pinfunction "P1_1") (pintype "passive"))
      (node (ref "SW1") (pin "4") (pinfunction "P1_4") (pintype "passive"))
    )
    (net (code "47") (name "Net-(U1-VDDANA)") (class "Default")
      (node (ref "C12") (pin "2") (pinfunction "2_2") (pintype "passive"))
      (node (ref "FB") (pin "1") (pinfunction "1_1") (pintype "passive"))
      (node (ref "U1") (pin "6") (pinfunction "VDDANA_6") (pintype "power_in"))
    )
    (net (code "48") (name "Net-(U1-VDDCORE)") (class "Default")
      (node (ref "C10") (pin "2") (pinfunction "2_2") (pintype "passive"))
      (node (ref "U1") (pin "43") (pinfunction "VDDCORE_43") (pintype "power_in"))
    )
    (net (code "49") (name "Net-(U2-BST)") (class "Default")
      (node (ref "C4") (pin "1") (pinfunction "1_1") (pintype "passive"))
      (node (ref "U2") (pin "5") (pinfunction "BST_5") (pintype "bidirectional"))
    )
    (net (code "50") (name "Net-(U2-EN{slash}SYNC)") (class "Default")
      (node (ref "R1") (pin "1") (pinfunction "1_1") (pintype "passive"))
      (node (ref "U2") (pin "6") (pinfunction "EN/SYNC_6") (pintype "bidirectional"))
    )
    (net (code "51") (name "Net-(U2-FB)") (class "Default")
      (node (ref "C5") (pin "1") (pinfunction "1_1") (pintype "passive"))
      (node (ref "R2") (pin "2") (pinfunction "2_2") (pintype "passive"))
      (node (ref "R3") (pin "1") (pinfunction "1_1") (pintype "passive"))
      (node (ref "U2") (pin "8") (pinfunction "FB_8") (pintype "bidirectional"))
    )
    (net (code "52") (name "Net-(U2-SW)") (class "Default")
      (node (ref "C4") (pin "2") (pinfunction "2_2") (pintype "passive"))
      (node (ref "L1") (pin "1") (pinfunction "1_1") (pintype "passive"))
      (node (ref "U2") (pin "3") (pinfunction "SW_3") (pintype "bidirectional"))
    )
    (net (code "53") (name "Net-(U2-VCC)") (class "Default")
      (node (ref "C3") (pin "2") (pinfunction "2_2") (pintype "passive"))
      (node (ref "U2") (pin "7") (pinfunction "VCC_7") (pintype "bidirectional"))
    )
    (net (code "54") (name "Net-(U4-CPOUT)") (class "Default")
      (node (ref "C17") (pin "2") (pinfunction "2_2") (pintype "passive"))
      (node (ref "U4") (pin "20") (pinfunction "CPOUT_20") (pintype "passive"))
    )
    (net (code "55") (name "Net-(U4-REGOUT)") (class "Default")
      (node (ref "C15") (pin "2") (pinfunction "2_2") (pintype "passive"))
      (node (ref "U4") (pin "10") (pinfunction "REGOUT_10") (pintype "passive"))
    )
    (net (code "56") (name "Net-(U5-ILIM)") (class "Default")
      (node (ref "R7") (pin "1") (pinfunction "1_1") (pintype "passive"))
      (node (ref "U5") (pin "4") (pinfunction "ILIM_4") (pintype "input"))
    )
    (net (code "57") (name "Net-(U5-OUT1)") (class "Default")
      (node (ref "J2") (pin "1") (pinfunction "1_1") (pintype "passive"))
      (node (ref "U5") (pin "6") (pinfunction "OUT1_6") (pintype "output"))
    )
    (net (code "58") (name "Net-(U5-OUT2)") (class "Default")
      (node (ref "J2") (pin "2") (pinfunction "2_2") (pintype "passive"))
      (node (ref "U5") (pin "8") (pinfunction "OUT2_8") (pintype "output"))
    )
    (net (code "59") (name "Net-(U6-ILIM)") (class "Default")
      (node (ref "R8") (pin "1") (pinfunction "1_1") (pintype "passive"))
      (node (ref "U6") (pin "4") (pinfunction "ILIM_4") (pintype "input"))
    )
    (net (code "60") (name "Net-(U6-OUT1)") (class "Default")
      (node (ref "J3") (pin "1") (pinfunction "1_1") (pintype "passive"))
      (node (ref "U6") (pin "6") (pinfunction "OUT1_6") (pintype "output"))
    )
    (net (code "61") (name "Net-(U6-OUT2)") (class "Default")
      (node (ref "J3") (pin "2") (pinfunction "2_2") (pintype "passive"))
      (node (ref "U6") (pin "8") (pinfunction "OUT2_8") (pintype "output"))
    )
    (net (code "62") (name "Net-(U7-B2)") (class "Default")
      (node (ref "J8") (pin "1") (pinfunction "1_1") (pintype "passive"))
      (node (ref "U7") (pin "12") (pinfunction "B2_12") (pintype "bidirectional"))
    )
    (net (code "63") (name "Net-(U7-B3)") (class "Default")
      (node (ref "J9") (pin "1") (pinfunction "1_1") (pintype "passive"))
      (node (ref "U7") (pin "11") (pinfunction "B3_11") (pintype "bidirectional"))
    )
    (net (code "64") (name "Net-(U7-B4)") (class "Default")
      (node (ref "J10") (pin "1") (pinfunction "1_1") (pintype "passive"))
      (node (ref "U7") (pin "10") (pinfunction "B4_10") (pintype "bidirectional"))
    )
    (net (code "65") (name "RX") (class "Default")
      (node (ref "J17") (pin "P$3") (pinfunction "3_P$3") (pintype "passive"))
      (node (ref "U1") (pin "20") (pinfunction "PB11_20") (pintype "bidirectional"))
    )
    (net (code "66") (name "SCL1") (class "Default")
      (node (ref "J15") (pin "21") (pinfunction "21_21") (pintype "passive"))
      (node (ref "J15") (pin "22") (pinfunction "22_22") (pintype "passive"))
      (node (ref "J6") (pin "1") (pinfunction "1_1") (pintype "passive"))
      (node (ref "J7") (pin "1") (pinfunction "1_1") (pintype "passive"))
      (node (ref "R11") (pin "8") (pinfunction "8_8") (pintype "passive"))
      (node (ref "U1") (pin "26") (pinfunction "PA17_26") (pintype "bidirectional"))
    )
    (net (code "67") (name "SCL2") (class "Default")
      (node (ref "J16") (pin "P$2") (pinfunction "2_P$2") (pintype "passive"))
      (node (ref "R11") (pin "5") (pinfunction "5_5") (pintype "passive"))
      (node (ref "U1") (pin "22") (pinfunction "PA13_22") (pintype "bidirectional"))
      (node (ref "U4") (pin "23") (pinfunction "SCL_23") (pintype "input"))
    )
    (net (code "68") (name "SDA1") (class "Default")
      (node (ref "J15") (pin "23") (pinfunction "23_23") (pintype "passive"))
      (node (ref "J15") (pin "24") (pinfunction "24_24") (pintype "passive"))
      (node (ref "J6") (pin "2") (pinfunction "2_2") (pintype "passive"))
      (node (ref "J7") (pin "2") (pinfunction "2_2") (pintype "passive"))
      (node (ref "R11") (pin "7") (pinfunction "7_7") (pintype "passive"))
      (node (ref "U1") (pin "25") (pinfunction "PA16_25") (pintype "bidirectional"))
    )
    (net (code "69") (name "SDA2") (class "Default")
      (node (ref "J16") (pin "P$3") (pinfunction "3_P$3") (pintype "passive"))
      (node (ref "R11") (pin "6") (pinfunction "6_6") (pintype "passive"))
      (node (ref "U1") (pin "21") (pinfunction "PA12_21") (pintype "bidirectional"))
      (node (ref "U4") (pin "24") (pinfunction "SDA_24") (pintype "bidirectional"))
    )
    (net (code "70") (name "SERVO1") (class "Default")
      (node (ref "J12") (pin "1") (pinfunction "1_1") (pintype "passive"))
      (node (ref "U1") (pin "2") (pinfunction "PA01_2") (pintype "bidirectional"))
    )
    (net (code "71") (name "SERVO2") (class "Default")
      (node (ref "J12") (pin "4") (pinfunction "4_4") (pintype "passive"))
      (node (ref "U1") (pin "1") (pinfunction "PA00_1") (pintype "bidirectional"))
    )
    (net (code "72") (name "SERVO3") (class "Default")
      (node (ref "J12") (pin "7") (pinfunction "7_7") (pintype "passive"))
      (node (ref "U1") (pin "13") (pinfunction "PA08_13") (pintype "bidirectional"))
    )
    (net (code "73") (name "SERVO4") (class "Default")
      (node (ref "J12") (pin "10") (pinfunction "10_10") (pintype "passive"))
      (node (ref "U1") (pin "14") (pinfunction "PA09_14") (pintype "bidirectional"))
    )
    (net (code "74") (name "SONAR1ECHO") (class "Default")
      (node (ref "U1") (pin "41") (pinfunction "PA28_41") (pintype "bidirectional"))
      (node (ref "U7") (pin "5") (pinfunction "A4_5") (pintype "bidirectional"))
    )
    (net (code "75") (name "SONAR1TRIG") (class "Default")
      (node (ref "J10") (pin "2") (pinfunction "2_2") (pintype "passive"))
      (node (ref "U1") (pin "39") (pinfunction "PA27_39") (pintype "bidirectional"))
    )
    (net (code "76") (name "SONAR2ECHO") (class "Default")
      (node (ref "U1") (pin "47") (pinfunction "PB02_47") (pintype "bidirectional"))
      (node (ref "U7") (pin "4") (pinfunction "A3_4") (pintype "bidirectional"))
    )
    (net (code "77") (name "SONAR2TRIG") (class "Default")
      (node (ref "J9") (pin "2") (pinfunction "2_2") (pintype "passive"))
      (node (ref "U1") (pin "38") (pinfunction "PB23_38") (pintype "bidirectional"))
    )
    (net (code "78") (name "SONAR3ECHO") (class "Default")
      (node (ref "U1") (pin "48") (pinfunction "PB03_48") (pintype "bidirectional"))
      (node (ref "U7") (pin "3") (pinfunction "A2_3") (pintype "bidirectional"))
    )
    (net (code "79") (name "SONAR3TRIG") (class "Default")
      (node (ref "J8") (pin "2") (pinfunction "2_2") (pintype "passive"))
      (node (ref "U1") (pin "37") (pinfunction "PB22_37") (pintype "bidirectional"))
    )
    (net (code "80") (name "SWCLK") (class "Default")
      (node (ref "R109") (pin "2") (pinfunction "2_2") (pintype "passive"))
      (node (ref "TP2") (pin "TP") (pinfunction "TP_TP") (pintype "input"))
      (node (ref "U1") (pin "45") (pinfunction "PA30_45") (pintype "bidirectional"))
    )
    (net (code "81") (name "SWDIO") (class "Default")
      (node (ref "TP3") (pin "TP") (pinfunction "TP_TP") (pintype "input"))
      (node (ref "U1") (pin "46") (pinfunction "PA31_46") (pintype "bidirectional"))
    )
    (net (code "82") (name "TX") (class "Default")
      (node (ref "J17") (pin "P$2") (pinfunction "2_P$2") (pintype "passive"))
      (node (ref "U1") (pin "19") (pinfunction "PB10_19") (pintype "bidirectional"))
    )
    (net (code "83") (name "VSENSE") (class "Default")
      (node (ref "R5") (pin "1") (pinfunction "1_1") (pintype "passive"))
      (node (ref "R6") (pin "1") (pinfunction "1_1") (pintype "passive"))
      (node (ref "U1") (pin "12") (pinfunction "PA07_12") (pintype "bidirectional"))
    )
    (net (code "84") (name "unconnected-(J15-Pad1)") (class "Default")
      (node (ref "J15") (pin "1") (pinfunction "1_1") (pintype "passive"))
    )
    (net (code "85") (name "unconnected-(J15-Pad5)") (class "Default")
      (node (ref "J15") (pin "5") (pinfunction "5_5") (pintype "passive"))
    )
    (net (code "86") (name "unconnected-(J17-4-PadP$4)") (class "Default")
      (node (ref "J17") (pin "P$4") (pinfunction "4_P$4") (pintype "passive"))
    )
    (net (code "87") (name "unconnected-(J17-5-PadP$5)") (class "Default")
      (node (ref "J17") (pin "P$5") (pinfunction "5_P$5") (pintype "passive"))
    )
    (net (code "88") (name "unconnected-(U1-PA03-Pad4)") (class "Default")
      (node (ref "U1") (pin "4") (pinfunction "PA03_4") (pintype "bidirectional"))
    )
    (net (code "89") (name "unconnected-(U1-PA11-Pad16)") (class "Default")
      (node (ref "U1") (pin "16") (pinfunction "PA11_16") (pintype "bidirectional"))
    )
    (net (code "90") (name "unconnected-(U4-AUX_CL-Pad7)") (class "Default")
      (node (ref "U4") (pin "7") (pinfunction "AUX_CL_7") (pintype "input"))
    )
    (net (code "91") (name "unconnected-(U4-AUX_DA-Pad6)") (class "Default")
      (node (ref "U4") (pin "6") (pinfunction "AUX_DA_6") (pintype "bidirectional"))
    )
    (net (code "92") (name "unconnected-(U4-INT-Pad12)") (class "Default")
      (node (ref "U4") (pin "12") (pinfunction "INT_12") (pintype "output"))
    )
    (net (code "93") (name "unconnected-(U4-RESV-Pad19)") (class "Default")
      (node (ref "U4") (pin "19") (pinfunction "RESV_19") (pintype "passive"))
    )
    (net (code "94") (name "unconnected-(U4-RESV-Pad21)") (class "Default")
      (node (ref "U4") (pin "21") (pinfunction "RESV_21") (pintype "passive"))
    )
    (net (code "95") (name "unconnected-(U4-RESV-Pad22)") (class "Default")
      (node (ref "U4") (pin "22") (pinfunction "RESV_22") (pintype "passive"))
    )
    (net (code "96") (name "unconnected-(U7-A1-Pad2)") (class "Default")
      (node (ref "U7") (pin "2") (pinfunction "A1_2") (pintype "bidirectional"))
    )
    (net (code "97") (name "unconnected-(U7-B1-Pad13)") (class "Default")
      (node (ref "U7") (pin "13") (pinfunction "B1_13") (pintype "bidirectional"))
    )
    (net (code "98") (name "unconnected-(U7-NC-Pad9)") (class "Default")
      (node (ref "U7") (pin "9") (pinfunction "NC_9") (pintype "no_connect"))
    )
    (net (code "99") (name "unconnected-(U7-NC_2-Pad6)") (class "Default")
      (node (ref "U7") (pin "6") (pinfunction "NC_2_6") (pintype "no_connect"))
    )
    (net (code "100") (name "unconnected-(USB1-ID-Pad4)") (class "Default")
      (node (ref "USB1") (pin "4") (pinfunction "ID_4") (pintype "bidirectional"))
    )
    (net (code "101") (name "unconnected-(USB1-VCC-Pad1)") (class "Default")
      (node (ref "USB1") (pin "1") (pinfunction "VCC_1") (pintype "bidirectional"))
    )
    (net (code "102") (name "~{RESET}") (class "Default")
      (node (ref "C14") (pin "1") (pinfunction "1_1") (pintype "passive"))
      (node (ref "J14") (pin "1") (pinfunction "1_1") (pintype "passive"))
      (node (ref "J14") (pin "2") (pinfunction "2_2") (pintype "passive"))
      (node (ref "R10") (pin "2") (pinfunction "2_2") (pintype "passive"))
      (node (ref "TP1") (pin "TP") (pinfunction "TP_TP") (pintype "input"))
      (node (ref "U1") (pin "40") (pinfunction "RSTN_40") (pintype "bidirectional"))
    )
  )
)
